# RemoteControl.net
KiCad netlist of a schematic drawn in EAGLE
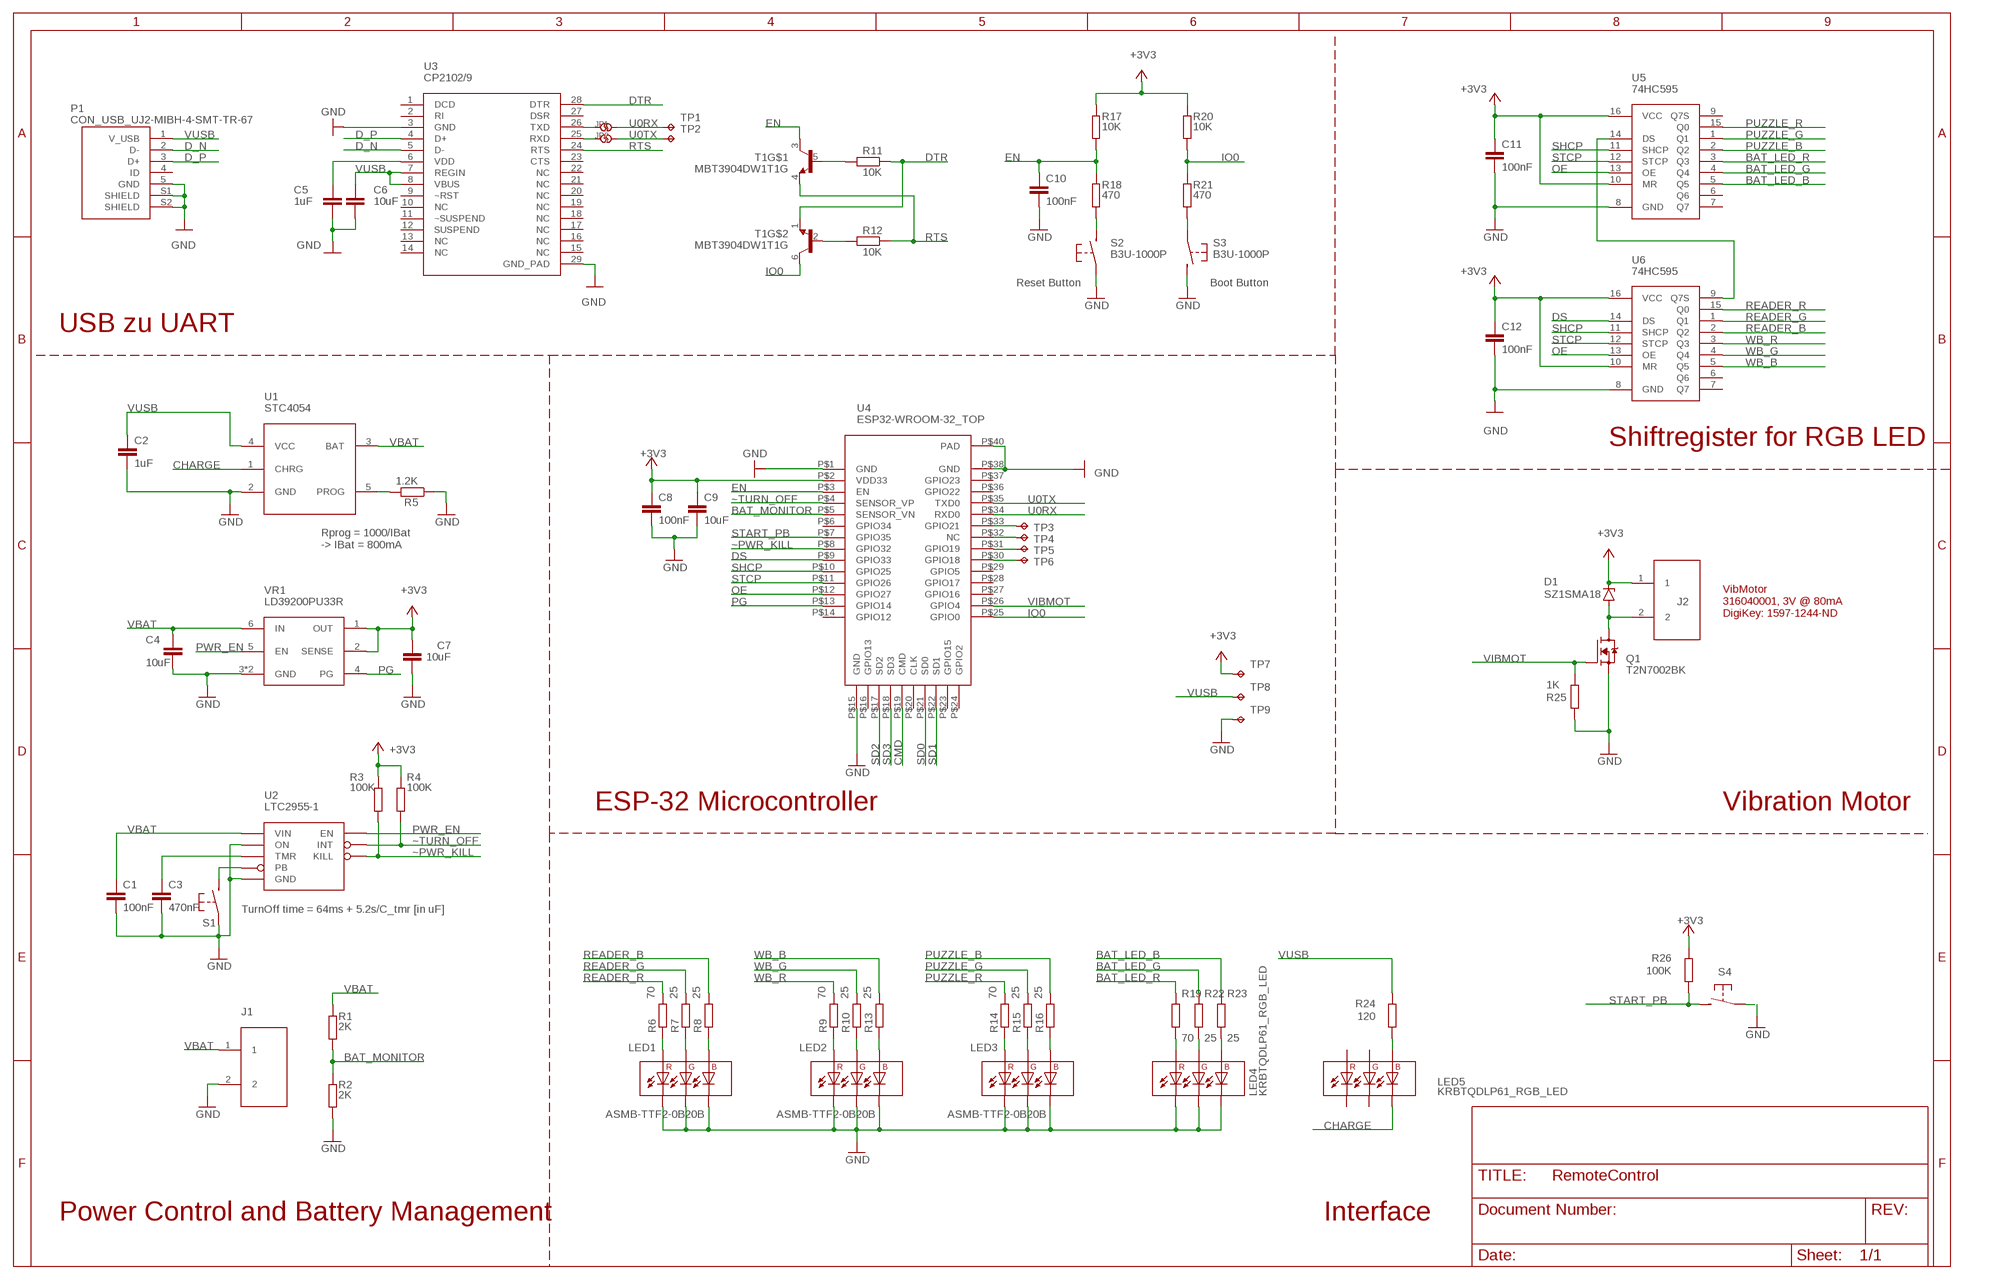
[diagram p0: schematic, sheet 1]

(export (version "E")
  (design (tool "Eeschema 10.0.6"))
  (components
    (comp (ref "C1")
      (value "100nF")
      (footprint "eagle-import:0603")
      (libsource (lib "eagle-import") (part "CAP_0603"))
    )
    (comp (ref "C2")
      (value "1uF")
      (footprint "eagle-import:0603")
      (libsource (lib "eagle-import") (part "CAP_0603"))
    )
    (comp (ref "C3")
      (value "470nF")
      (footprint "eagle-import:0603")
      (libsource (lib "eagle-import") (part "CAP_0603"))
    )
    (comp (ref "C4")
      (value "10uF")
      (footprint "eagle-import:0603")
      (libsource (lib "eagle-import") (part "CAP_0603"))
    )
    (comp (ref "C5")
      (value "1uF")
      (footprint "eagle-import:0603")
      (libsource (lib "eagle-import") (part "CAP_0603"))
    )
    (comp (ref "C6")
      (value "10uF")
      (footprint "eagle-import:0603")
      (libsource (lib "eagle-import") (part "CAP_0603"))
    )
    (comp (ref "C7")
      (value "10uF")
      (footprint "eagle-import:0603")
      (libsource (lib "eagle-import") (part "CAP_0603"))
    )
    (comp (ref "C8")
      (value "100nF")
      (footprint "eagle-import:0603")
      (libsource (lib "eagle-import") (part "CAP_0603"))
    )
    (comp (ref "C9")
      (value "10uF")
      (footprint "eagle-import:0603")
      (libsource (lib "eagle-import") (part "CAP_0603"))
    )
    (comp (ref "C10")
      (value "100nF")
      (footprint "eagle-import:0603")
      (libsource (lib "eagle-import") (part "CAP_0603"))
    )
    (comp (ref "C11")
      (value "100nF")
      (footprint "eagle-import:0603")
      (libsource (lib "eagle-import") (part "CAP_0603"))
    )
    (comp (ref "C12")
      (value "100nF")
      (footprint "eagle-import:0603")
      (libsource (lib "eagle-import") (part "CAP_0603"))
    )
    (comp (ref "D1")
      (value "SZ1SMA18")
      (footprint "eagle-import:SMA-2")
      (libsource (lib "eagle-import") (part "SZ1SMA18AT3G_Z_DIODE"))
    )
    (comp (ref "J1")
      (value "CON_2")
      (footprint "eagle-import:CON_2")
      (libsource (lib "eagle-import") (part "CON_2"))
    )
    (comp (ref "J2")
      (value "CON_2")
      (footprint "eagle-import:CON_2")
      (libsource (lib "eagle-import") (part "CON_2"))
    )
    (comp (ref "JP1")
      (value "SOLDER_JUMPER")
      (footprint "eagle-import:SOLDER_JUMPER")
      (libsource (lib "eagle-import") (part "SOLDER_JUMPER"))
    )
    (comp (ref "JP2")
      (value "SOLDER_JUMPER")
      (footprint "eagle-import:SOLDER_JUMPER")
      (libsource (lib "eagle-import") (part "SOLDER_JUMPER"))
    )
    (comp (ref "LED1")
      (value "ASMB-TTF2-0B20B")
      (footprint "eagle-import:ASMB-TTF2-0B20B_RGB_LED")
      (libsource (lib "eagle-import") (part "ASMB-TTF2-0B20B_RGB_LED"))
    )
    (comp (ref "LED2")
      (value "ASMB-TTF2-0B20B")
      (footprint "eagle-import:ASMB-TTF2-0B20B_RGB_LED")
      (libsource (lib "eagle-import") (part "ASMB-TTF2-0B20B_RGB_LED"))
    )
    (comp (ref "LED3")
      (value "ASMB-TTF2-0B20B")
      (footprint "eagle-import:ASMB-TTF2-0B20B_RGB_LED")
      (libsource (lib "eagle-import") (part "ASMB-TTF2-0B20B_RGB_LED"))
    )
    (comp (ref "LED4")
      (value "KRBTQDLP61_RGB_LED")
      (footprint "eagle-import:KRBTQDLP61_RGB_LED")
      (libsource (lib "eagle-import") (part "KRBTQDLP61_RGB_LED"))
    )
    (comp (ref "LED5")
      (value "KRBTQDLP61_RGB_LED")
      (footprint "eagle-import:KRBTQDLP61_RGB_LED")
      (libsource (lib "eagle-import") (part "KRBTQDLP61_RGB_LED"))
    )
    (comp (ref "P1")
      (value "CON_USB_UJ2-MIBH-4-SMT-TR-67")
      (footprint "eagle-import:CON_USB_UJ2-MIBH-4-SMT-TR-67")
      (libsource (lib "eagle-import") (part "CON_USB_UJ2-MIBH-4-SMT-TR-67"))
    )
    (comp (ref "Q1")
      (value "T2N7002BK")
      (footprint "eagle-import:SOT23-3")
      (libsource (lib "eagle-import") (part "T2N7002BK"))
    )
    (comp (ref "R1")
      (value "2K")
      (footprint "eagle-import:0603")
      (libsource (lib "eagle-import") (part "RES_0603"))
    )
    (comp (ref "R2")
      (value "2K")
      (footprint "eagle-import:0603")
      (libsource (lib "eagle-import") (part "RES_0603"))
    )
    (comp (ref "R3")
      (value "100K")
      (footprint "eagle-import:0603")
      (libsource (lib "eagle-import") (part "RES_0603"))
    )
    (comp (ref "R4")
      (value "100K")
      (footprint "eagle-import:0603")
      (libsource (lib "eagle-import") (part "RES_0603"))
    )
    (comp (ref "R5")
      (value "1.2K")
      (footprint "eagle-import:0603")
      (libsource (lib "eagle-import") (part "RES_0603"))
    )
    (comp (ref "R6")
      (value "70")
      (footprint "eagle-import:0603")
      (libsource (lib "eagle-import") (part "RES_0603"))
    )
    (comp (ref "R7")
      (value "25")
      (footprint "eagle-import:0603")
      (libsource (lib "eagle-import") (part "RES_0603"))
    )
    (comp (ref "R8")
      (value "25")
      (footprint "eagle-import:0603")
      (libsource (lib "eagle-import") (part "RES_0603"))
    )
    (comp (ref "R9")
      (value "70")
      (footprint "eagle-import:0603")
      (libsource (lib "eagle-import") (part "RES_0603"))
    )
    (comp (ref "R10")
      (value "25")
      (footprint "eagle-import:0603")
      (libsource (lib "eagle-import") (part "RES_0603"))
    )
    (comp (ref "R11")
      (value "10K")
      (footprint "eagle-import:0603")
      (libsource (lib "eagle-import") (part "RES_0603"))
    )
    (comp (ref "R12")
      (value "10K")
      (footprint "eagle-import:0603")
      (libsource (lib "eagle-import") (part "RES_0603"))
    )
    (comp (ref "R13")
      (value "25")
      (footprint "eagle-import:0603")
      (libsource (lib "eagle-import") (part "RES_0603"))
    )
    (comp (ref "R14")
      (value "70")
      (footprint "eagle-import:0603")
      (libsource (lib "eagle-import") (part "RES_0603"))
    )
    (comp (ref "R15")
      (value "25")
      (footprint "eagle-import:0603")
      (libsource (lib "eagle-import") (part "RES_0603"))
    )
    (comp (ref "R16")
      (value "25")
      (footprint "eagle-import:0603")
      (libsource (lib "eagle-import") (part "RES_0603"))
    )
    (comp (ref "R17")
      (value "10K")
      (footprint "eagle-import:0603")
      (libsource (lib "eagle-import") (part "RES_0603"))
    )
    (comp (ref "R18")
      (value "470")
      (footprint "eagle-import:0603")
      (libsource (lib "eagle-import") (part "RES_0603"))
    )
    (comp (ref "R19")
      (value "70")
      (footprint "eagle-import:0603")
      (libsource (lib "eagle-import") (part "RES_0603"))
    )
    (comp (ref "R20")
      (value "10K")
      (footprint "eagle-import:0603")
      (libsource (lib "eagle-import") (part "RES_0603"))
    )
    (comp (ref "R21")
      (value "470")
      (footprint "eagle-import:0603")
      (libsource (lib "eagle-import") (part "RES_0603"))
    )
    (comp (ref "R22")
      (value "25")
      (footprint "eagle-import:0603")
      (libsource (lib "eagle-import") (part "RES_0603"))
    )
    (comp (ref "R23")
      (value "25")
      (footprint "eagle-import:0603")
      (libsource (lib "eagle-import") (part "RES_0603"))
    )
    (comp (ref "R24")
      (value "120")
      (footprint "eagle-import:0603")
      (libsource (lib "eagle-import") (part "RES_0603"))
    )
    (comp (ref "R25")
      (value "1K")
      (footprint "eagle-import:0603")
      (libsource (lib "eagle-import") (part "RES_0603"))
    )
    (comp (ref "R26")
      (value "100K")
      (footprint "eagle-import:0603")
      (libsource (lib "eagle-import") (part "RES_0603"))
    )
    (comp (ref "S1")
      (value "EG5358CT-ND_PB")
      (footprint "eagle-import:EG5358CT-ND_PB")
      (libsource (lib "eagle-import") (part "EG5358CT-ND_PB"))
    )
    (comp (ref "S2")
      (value "B3U-1000P")
      (footprint "eagle-import:B3U-1000P")
      (libsource (lib "eagle-import") (part "BUTTON_B3U-1000P"))
    )
    (comp (ref "S3")
      (value "B3U-1000P")
      (footprint "eagle-import:B3U-1000P")
      (libsource (lib "eagle-import") (part "BUTTON_B3U-1000P"))
    )
    (comp (ref "S4")
      (value "TL3313AF160QG_2")
      (footprint "eagle-import:TL3313AF160QG_2")
      (libsource (lib "eagle-import") (part "BUTTON_TL3313AF160QG_2"))
    )
    (comp (ref "T1")
      (value "MBT3904DW1T1G")
      (footprint "eagle-import:SOT23-6")
      (libsource (lib "eagle-import") (part "MBT3904DW1T1G"))
    )
    (comp (ref "TP1")
      (value "TP")
      (footprint "eagle-import:TEST_PAD")
      (libsource (lib "eagle-import") (part "TP"))
    )
    (comp (ref "TP2")
      (value "TP")
      (footprint "eagle-import:TEST_PAD")
      (libsource (lib "eagle-import") (part "TP"))
    )
    (comp (ref "TP3")
      (value "TP")
      (footprint "eagle-import:TEST_PAD")
      (libsource (lib "eagle-import") (part "TP"))
    )
    (comp (ref "TP4")
      (value "TP")
      (footprint "eagle-import:TEST_PAD")
      (libsource (lib "eagle-import") (part "TP"))
    )
    (comp (ref "TP5")
      (value "TP")
      (footprint "eagle-import:TEST_PAD")
      (libsource (lib "eagle-import") (part "TP"))
    )
    (comp (ref "TP6")
      (value "TP")
      (footprint "eagle-import:TEST_PAD")
      (libsource (lib "eagle-import") (part "TP"))
    )
    (comp (ref "TP7")
      (value "TP")
      (footprint "eagle-import:TEST_PAD")
      (libsource (lib "eagle-import") (part "TP"))
    )
    (comp (ref "TP8")
      (value "TP")
      (footprint "eagle-import:TEST_PAD")
      (libsource (lib "eagle-import") (part "TP"))
    )
    (comp (ref "TP9")
      (value "TP")
      (footprint "eagle-import:TEST_PAD")
      (libsource (lib "eagle-import") (part "TP"))
    )
    (comp (ref "U1")
      (value "STC4054")
      (footprint "eagle-import:TSOT23-5L")
      (libsource (lib "eagle-import") (part "STC4054_BAT_CHARGER"))
    )
    (comp (ref "U2")
      (value "LTC2955-1")
      (footprint "eagle-import:SOT23-8")
      (libsource (lib "eagle-import") (part "LTC2955-1_ON/OFF_CTLR"))
    )
    (comp (ref "U3")
      (value "CP2102/9")
      (footprint "eagle-import:QFN-28")
      (libsource (lib "eagle-import") (part "CP2102/9"))
    )
    (comp (ref "U4")
      (value "ESP32-WROOM-32_TOP")
      (footprint "eagle-import:ESP32-WROOM-32_TOP")
      (libsource (lib "eagle-import") (part "ESP32-WROOM-32_TOP"))
    )
    (comp (ref "U5")
      (value "74HC595")
      (footprint "eagle-import:SOIC-16")
      (libsource (lib "eagle-import") (part "74HC595_SHIFTREGISTER"))
    )
    (comp (ref "U6")
      (value "74HC595")
      (footprint "eagle-import:SOIC-16")
      (libsource (lib "eagle-import") (part "74HC595_SHIFTREGISTER"))
    )
    (comp (ref "VR1")
      (value "LD39200PU33R")
      (footprint "eagle-import:DFN-6")
      (libsource (lib "eagle-import") (part "LD39200PU33R_V-REG"))
    )
  )
  (nets
    (net (code "1") (name "+3V3") (class "Default")
      (node (ref "C11") (pin "1") (pinfunction "1_1") (pintype "passive"))
      (node (ref "C12") (pin "1") (pinfunction "1_1") (pintype "passive"))
      (node (ref "C7") (pin "2") (pinfunction "2_2") (pintype "passive"))
      (node (ref "C8") (pin "1") (pinfunction "1_1") (pintype "passive"))
      (node (ref "C9") (pin "1") (pinfunction "1_1") (pintype "passive"))
      (node (ref "D1") (pin "1") (pinfunction "C_1") (pintype "passive"))
      (node (ref "J2") (pin "1") (pinfunction "1_1") (pintype "bidirectional"))
      (node (ref "R17") (pin "2") (pinfunction "2_2") (pintype "passive"))
      (node (ref "R20") (pin "2") (pinfunction "2_2") (pintype "passive"))
      (node (ref "R26") (pin "2") (pinfunction "2_2") (pintype "passive"))
      (node (ref "R3") (pin "1") (pinfunction "1_1") (pintype "passive"))
      (node (ref "R4") (pin "1") (pinfunction "1_1") (pintype "passive"))
      (node (ref "TP7") (pin "TP") (pinfunction "TP_TP") (pintype "input"))
      (node (ref "U4") (pin "P$2") (pinfunction "VDD33_P$2") (pintype "bidirectional"))
      (node (ref "U5") (pin "10") (pinfunction "MR_10") (pintype "bidirectional"))
      (node (ref "U5") (pin "16") (pinfunction "VCC_16") (pintype "bidirectional"))
      (node (ref "U6") (pin "10") (pinfunction "MR_10") (pintype "bidirectional"))
      (node (ref "U6") (pin "16") (pinfunction "VCC_16") (pintype "bidirectional"))
      (node (ref "VR1") (pin "1") (pinfunction "OUT_1") (pintype "bidirectional"))
      (node (ref "VR1") (pin "2") (pinfunction "SENSE_2") (pintype "bidirectional"))
    )
    (net (code "2") (name "/BAT_LED_B") (class "Default")
      (node (ref "R23") (pin "2") (pinfunction "2_2") (pintype "passive"))
      (node (ref "U5") (pin "5") (pinfunction "Q5_5") (pintype "bidirectional"))
    )
    (net (code "3") (name "/BAT_LED_G") (class "Default")
      (node (ref "R22") (pin "2") (pinfunction "2_2") (pintype "passive"))
      (node (ref "U5") (pin "4") (pinfunction "Q4_4") (pintype "bidirectional"))
    )
    (net (code "4") (name "/BAT_LED_R") (class "Default")
      (node (ref "R19") (pin "2") (pinfunction "2_2") (pintype "passive"))
      (node (ref "U5") (pin "3") (pinfunction "Q3_3") (pintype "bidirectional"))
    )
    (net (code "5") (name "/BAT_MONITOR") (class "Default")
      (node (ref "R1") (pin "2") (pinfunction "2_2") (pintype "passive"))
      (node (ref "R2") (pin "1") (pinfunction "1_1") (pintype "passive"))
      (node (ref "U4") (pin "P$5") (pinfunction "SENSOR_VN_P$5") (pintype "bidirectional"))
    )
    (net (code "6") (name "/CHARGE") (class "Default")
      (node (ref "LED5") (pin "P$4") (pinfunction "BC_P$4") (pintype "passive"))
      (node (ref "U1") (pin "1") (pinfunction "CHRG_1") (pintype "bidirectional"))
    )
    (net (code "7") (name "/CMD") (class "Default")
      (node (ref "U4") (pin "P$19") (pinfunction "CMD_P$19") (pintype "bidirectional"))
    )
    (net (code "8") (name "/DS") (class "Default")
      (node (ref "U4") (pin "P$9") (pinfunction "GPIO33_P$9") (pintype "bidirectional"))
      (node (ref "U6") (pin "14") (pinfunction "DS_14") (pintype "bidirectional"))
    )
    (net (code "9") (name "/DTR") (class "Default")
      (node (ref "R11") (pin "1") (pinfunction "1_1") (pintype "passive"))
      (node (ref "T1") (pin "1") (pinfunction "E_1") (pintype "passive"))
      (node (ref "U3") (pin "28") (pinfunction "DTR_28") (pintype "bidirectional"))
    )
    (net (code "10") (name "/D_N") (class "Default")
      (node (ref "P1") (pin "2") (pinfunction "D-_2") (pintype "bidirectional"))
      (node (ref "U3") (pin "5") (pinfunction "D-_5") (pintype "bidirectional"))
    )
    (net (code "11") (name "/D_P") (class "Default")
      (node (ref "P1") (pin "3") (pinfunction "D+_3") (pintype "bidirectional"))
      (node (ref "U3") (pin "4") (pinfunction "D+_4") (pintype "bidirectional"))
    )
    (net (code "12") (name "/EN") (class "Default")
      (node (ref "C10") (pin "1") (pinfunction "1_1") (pintype "passive"))
      (node (ref "R17") (pin "1") (pinfunction "1_1") (pintype "passive"))
      (node (ref "R18") (pin "2") (pinfunction "2_2") (pintype "passive"))
      (node (ref "T1") (pin "3") (pinfunction "C_3") (pintype "passive"))
      (node (ref "U4") (pin "P$3") (pinfunction "EN_P$3") (pintype "bidirectional"))
    )
    (net (code "13") (name "/IO0") (class "Default")
      (node (ref "R20") (pin "1") (pinfunction "1_1") (pintype "passive"))
      (node (ref "R21") (pin "2") (pinfunction "2_2") (pintype "passive"))
      (node (ref "T1") (pin "6") (pinfunction "C_6") (pintype "passive"))
      (node (ref "U4") (pin "P$25") (pinfunction "GPIO0_P$25") (pintype "bidirectional"))
    )
    (net (code "14") (name "/OE") (class "Default")
      (node (ref "U4") (pin "P$12") (pinfunction "GPIO27_P$12") (pintype "bidirectional"))
      (node (ref "U5") (pin "13") (pinfunction "OE_13") (pintype "bidirectional"))
      (node (ref "U6") (pin "13") (pinfunction "OE_13") (pintype "bidirectional"))
    )
    (net (code "15") (name "/PG") (class "Default")
      (node (ref "U4") (pin "P$13") (pinfunction "GPIO14_P$13") (pintype "bidirectional"))
      (node (ref "VR1") (pin "4") (pinfunction "PG_4") (pintype "bidirectional"))
    )
    (net (code "16") (name "/PUZZLE_B") (class "Default")
      (node (ref "R16") (pin "2") (pinfunction "2_2") (pintype "passive"))
      (node (ref "U5") (pin "2") (pinfunction "Q2_2") (pintype "bidirectional"))
    )
    (net (code "17") (name "/PUZZLE_G") (class "Default")
      (node (ref "R15") (pin "2") (pinfunction "2_2") (pintype "passive"))
      (node (ref "U5") (pin "1") (pinfunction "Q1_1") (pintype "bidirectional"))
    )
    (net (code "18") (name "/PUZZLE_R") (class "Default")
      (node (ref "R14") (pin "2") (pinfunction "2_2") (pintype "passive"))
      (node (ref "U5") (pin "15") (pinfunction "Q0_15") (pintype "bidirectional"))
    )
    (net (code "19") (name "/PWR_EN") (class "Default")
      (node (ref "U2") (pin "7") (pinfunction "EN_7") (pintype "bidirectional"))
      (node (ref "VR1") (pin "5") (pinfunction "EN_5") (pintype "bidirectional"))
    )
    (net (code "20") (name "/READER_B") (class "Default")
      (node (ref "R8") (pin "2") (pinfunction "2_2") (pintype "passive"))
      (node (ref "U6") (pin "2") (pinfunction "Q2_2") (pintype "bidirectional"))
    )
    (net (code "21") (name "/READER_G") (class "Default")
      (node (ref "R7") (pin "2") (pinfunction "2_2") (pintype "passive"))
      (node (ref "U6") (pin "1") (pinfunction "Q1_1") (pintype "bidirectional"))
    )
    (net (code "22") (name "/READER_R") (class "Default")
      (node (ref "R6") (pin "2") (pinfunction "2_2") (pintype "passive"))
      (node (ref "U6") (pin "15") (pinfunction "Q0_15") (pintype "bidirectional"))
    )
    (net (code "23") (name "/RTS") (class "Default")
      (node (ref "R12") (pin "1") (pinfunction "1_1") (pintype "passive"))
      (node (ref "T1") (pin "4") (pinfunction "E_4") (pintype "passive"))
      (node (ref "U3") (pin "24") (pinfunction "RTS_24") (pintype "bidirectional"))
    )
    (net (code "24") (name "/SD0") (class "Default")
      (node (ref "U4") (pin "P$21") (pinfunction "SD0_P$21") (pintype "bidirectional"))
    )
    (net (code "25") (name "/SD1") (class "Default")
      (node (ref "U4") (pin "P$22") (pinfunction "SD1_P$22") (pintype "bidirectional"))
    )
    (net (code "26") (name "/SD2") (class "Default")
      (node (ref "U4") (pin "P$17") (pinfunction "SD2_P$17") (pintype "bidirectional"))
    )
    (net (code "27") (name "/SD3") (class "Default")
      (node (ref "U4") (pin "P$18") (pinfunction "SD3_P$18") (pintype "bidirectional"))
    )
    (net (code "28") (name "/SHCP") (class "Default")
      (node (ref "U4") (pin "P$10") (pinfunction "GPIO25_P$10") (pintype "bidirectional"))
      (node (ref "U5") (pin "11") (pinfunction "SHCP_11") (pintype "bidirectional"))
      (node (ref "U6") (pin "11") (pinfunction "SHCP_11") (pintype "bidirectional"))
    )
    (net (code "29") (name "/START_PB") (class "Default")
      (node (ref "R26") (pin "1") (pinfunction "1_1") (pintype "passive"))
      (node (ref "S4") (pin "3") (pinfunction "S_3") (pintype "passive"))
      (node (ref "S4") (pin "4") (pinfunction "S_4") (pintype "passive"))
      (node (ref "U4") (pin "P$7") (pinfunction "GPIO35_P$7") (pintype "bidirectional"))
    )
    (net (code "30") (name "/STCP") (class "Default")
      (node (ref "U4") (pin "P$11") (pinfunction "GPIO26_P$11") (pintype "bidirectional"))
      (node (ref "U5") (pin "12") (pinfunction "STCP_12") (pintype "bidirectional"))
      (node (ref "U6") (pin "12") (pinfunction "STCP_12") (pintype "bidirectional"))
    )
    (net (code "31") (name "/U0RX") (class "Default")
      (node (ref "JP1") (pin "P$2") (pinfunction "P$2_P$2") (pintype "bidirectional"))
      (node (ref "TP1") (pin "TP") (pinfunction "TP_TP") (pintype "input"))
      (node (ref "U4") (pin "P$34") (pinfunction "RXD0_P$34") (pintype "bidirectional"))
    )
    (net (code "32") (name "/U0TX") (class "Default")
      (node (ref "JP2") (pin "P$2") (pinfunction "P$2_P$2") (pintype "bidirectional"))
      (node (ref "TP2") (pin "TP") (pinfunction "TP_TP") (pintype "input"))
      (node (ref "U4") (pin "P$35") (pinfunction "TXD0_P$35") (pintype "bidirectional"))
    )
    (net (code "33") (name "/VBAT") (class "Default")
      (node (ref "C1") (pin "1") (pinfunction "1_1") (pintype "passive"))
      (node (ref "C4") (pin "1") (pinfunction "1_1") (pintype "passive"))
      (node (ref "J1") (pin "1") (pinfunction "1_1") (pintype "bidirectional"))
      (node (ref "R1") (pin "1") (pinfunction "1_1") (pintype "passive"))
      (node (ref "U1") (pin "3") (pinfunction "BAT_3") (pintype "bidirectional"))
      (node (ref "U2") (pin "6") (pinfunction "VIN_6") (pintype "bidirectional"))
      (node (ref "VR1") (pin "6") (pinfunction "IN_6") (pintype "bidirectional"))
    )
    (net (code "34") (name "/VIBMOT") (class "Default")
      (node (ref "Q1") (pin "1") (pinfunction "G_1") (pintype "passive"))
      (node (ref "R25") (pin "2") (pinfunction "2_2") (pintype "passive"))
      (node (ref "U4") (pin "P$26") (pinfunction "GPIO4_P$26") (pintype "bidirectional"))
    )
    (net (code "35") (name "/VUSB") (class "Default")
      (node (ref "C2") (pin "1") (pinfunction "1_1") (pintype "passive"))
      (node (ref "C6") (pin "1") (pinfunction "1_1") (pintype "passive"))
      (node (ref "P1") (pin "1") (pinfunction "V_USB_1") (pintype "bidirectional"))
      (node (ref "R24") (pin "2") (pinfunction "2_2") (pintype "passive"))
      (node (ref "TP8") (pin "TP") (pinfunction "TP_TP") (pintype "input"))
      (node (ref "U1") (pin "4") (pinfunction "VCC_4") (pintype "bidirectional"))
      (node (ref "U3") (pin "7") (pinfunction "REGIN_7") (pintype "bidirectional"))
      (node (ref "U3") (pin "8") (pinfunction "VBUS_8") (pintype "bidirectional"))
    )
    (net (code "36") (name "/WB_B") (class "Default")
      (node (ref "R13") (pin "2") (pinfunction "2_2") (pintype "passive"))
      (node (ref "U6") (pin "5") (pinfunction "Q5_5") (pintype "bidirectional"))
    )
    (net (code "37") (name "/WB_G") (class "Default")
      (node (ref "R10") (pin "2") (pinfunction "2_2") (pintype "passive"))
      (node (ref "U6") (pin "4") (pinfunction "Q4_4") (pintype "bidirectional"))
    )
    (net (code "38") (name "/WB_R") (class "Default")
      (node (ref "R9") (pin "2") (pinfunction "2_2") (pintype "passive"))
      (node (ref "U6") (pin "3") (pinfunction "Q3_3") (pintype "bidirectional"))
    )
    (net (code "39") (name "/~{PWR_KILL}") (class "Default")
      (node (ref "R3") (pin "2") (pinfunction "2_2") (pintype "passive"))
      (node (ref "U2") (pin "2") (pinfunction "KILL_2") (pintype "bidirectional"))
      (node (ref "U4") (pin "P$8") (pinfunction "GPIO32_P$8") (pintype "bidirectional"))
    )
    (net (code "40") (name "/~{TURN_OFF}") (class "Default")
      (node (ref "R4") (pin "2") (pinfunction "2_2") (pintype "passive"))
      (node (ref "U2") (pin "8") (pinfunction "INT_8") (pintype "bidirectional"))
      (node (ref "U4") (pin "P$4") (pinfunction "SENSOR_VP_P$4") (pintype "bidirectional"))
    )
    (net (code "41") (name "GND") (class "Default")
      (node (ref "C1") (pin "2") (pinfunction "2_2") (pintype "passive"))
      (node (ref "C10") (pin "2") (pinfunction "2_2") (pintype "passive"))
      (node (ref "C11") (pin "2") (pinfunction "2_2") (pintype "passive"))
      (node (ref "C12") (pin "2") (pinfunction "2_2") (pintype "passive"))
      (node (ref "C2") (pin "2") (pinfunction "2_2") (pintype "passive"))
      (node (ref "C3") (pin "2") (pinfunction "2_2") (pintype "passive"))
      (node (ref "C4") (pin "2") (pinfunction "2_2") (pintype "passive"))
      (node (ref "C5") (pin "2") (pinfunction "2_2") (pintype "passive"))
      (node (ref "C6") (pin "2") (pinfunction "2_2") (pintype "passive"))
      (node (ref "C7") (pin "1") (pinfunction "1_1") (pintype "passive"))
      (node (ref "C8") (pin "2") (pinfunction "2_2") (pintype "passive"))
      (node (ref "C9") (pin "2") (pinfunction "2_2") (pintype "passive"))
      (node (ref "J1") (pin "2") (pinfunction "2_2") (pintype "bidirectional"))
      (node (ref "LED1") (pin "BC") (pinfunction "BC_BC") (pintype "passive"))
      (node (ref "LED1") (pin "GC") (pinfunction "GC_GC") (pintype "passive"))
      (node (ref "LED1") (pin "RC") (pinfunction "RC_RC") (pintype "passive"))
      (node (ref "LED2") (pin "BC") (pinfunction "BC_BC") (pintype "passive"))
      (node (ref "LED2") (pin "GC") (pinfunction "GC_GC") (pintype "passive"))
      (node (ref "LED2") (pin "RC") (pinfunction "RC_RC") (pintype "passive"))
      (node (ref "LED3") (pin "BC") (pinfunction "BC_BC") (pintype "passive"))
      (node (ref "LED3") (pin "GC") (pinfunction "GC_GC") (pintype "passive"))
      (node (ref "LED3") (pin "RC") (pinfunction "RC_RC") (pintype "passive"))
      (node (ref "LED4") (pin "P$3") (pinfunction "GC_P$3") (pintype "passive"))
      (node (ref "LED4") (pin "P$4") (pinfunction "BC_P$4") (pintype "passive"))
      (node (ref "LED4") (pin "P$6") (pinfunction "RC_P$6") (pintype "passive"))
      (node (ref "P1") (pin "5") (pinfunction "GND_5") (pintype "bidirectional"))
      (node (ref "P1") (pin "S1") (pinfunction "SHIELD_S1") (pintype "bidirectional"))
      (node (ref "P1") (pin "S2") (pinfunction "SHIELD_S2") (pintype "bidirectional"))
      (node (ref "Q1") (pin "2") (pinfunction "S_2") (pintype "passive"))
      (node (ref "R2") (pin "2") (pinfunction "2_2") (pintype "passive"))
      (node (ref "R25") (pin "1") (pinfunction "1_1") (pintype "passive"))
      (node (ref "R5") (pin "1") (pinfunction "1_1") (pintype "passive"))
      (node (ref "S1") (pin "1") (pinfunction "P_1") (pintype "passive"))
      (node (ref "S1") (pin "S1") (pinfunction "P_S1") (pintype "passive"))
      (node (ref "S1") (pin "S2") (pinfunction "P_S2") (pintype "passive"))
      (node (ref "S2") (pin "P$1") (pinfunction "P_P$1") (pintype "passive"))
      (node (ref "S3") (pin "P$2") (pinfunction "S_P$2") (pintype "passive"))
      (node (ref "S4") (pin "1") (pinfunction "P_1") (pintype "passive"))
      (node (ref "S4") (pin "2") (pinfunction "P_2") (pintype "passive"))
      (node (ref "TP9") (pin "TP") (pinfunction "TP_TP") (pintype "input"))
      (node (ref "U1") (pin "2") (pinfunction "GND_2") (pintype "bidirectional"))
      (node (ref "U2") (pin "1") (pinfunction "ON_1") (pintype "bidirectional"))
      (node (ref "U2") (pin "4") (pinfunction "GND_4") (pintype "bidirectional"))
      (node (ref "U3") (pin "29") (pinfunction "GND_PAD_29") (pintype "bidirectional"))
      (node (ref "U3") (pin "3") (pinfunction "GND_3") (pintype "bidirectional"))
      (node (ref "U4") (pin "P$1") (pinfunction "GND_P$1") (pintype "bidirectional"))
      (node (ref "U4") (pin "P$15") (pinfunction "GND_P$15") (pintype "bidirectional"))
      (node (ref "U4") (pin "P$38") (pinfunction "GND_P$38") (pintype "bidirectional"))
      (node (ref "U4") (pin "P$40") (pinfunction "PAD_P$40") (pintype "bidirectional"))
      (node (ref "U5") (pin "8") (pinfunction "GND_8") (pintype "bidirectional"))
      (node (ref "U6") (pin "8") (pinfunction "GND_8") (pintype "bidirectional"))
      (node (ref "VR1") (pin "3") (pinfunction "GND_3") (pintype "bidirectional"))
      (node (ref "VR1") (pin "7") (pinfunction "GND_7") (pintype "bidirectional"))
    )
    (net (code "42") (name "Net-(D1-A)") (class "Default")
      (node (ref "D1") (pin "2") (pinfunction "A_2") (pintype "passive"))
      (node (ref "J2") (pin "2") (pinfunction "2_2") (pintype "bidirectional"))
      (node (ref "Q1") (pin "3") (pinfunction "D_3") (pintype "passive"))
    )
    (net (code "43") (name "Net-(LED1-PadBA)") (class "Default")
      (node (ref "LED1") (pin "BA") (pinfunction "BA_BA") (pintype "passive"))
      (node (ref "R8") (pin "1") (pinfunction "1_1") (pintype "passive"))
    )
    (net (code "44") (name "Net-(LED1-PadGA)") (class "Default")
      (node (ref "LED1") (pin "GA") (pinfunction "GA_GA") (pintype "passive"))
      (node (ref "R7") (pin "1") (pinfunction "1_1") (pintype "passive"))
    )
    (net (code "45") (name "Net-(LED1-PadRA)") (class "Default")
      (node (ref "LED1") (pin "RA") (pinfunction "RA_RA") (pintype "passive"))
      (node (ref "R6") (pin "1") (pinfunction "1_1") (pintype "passive"))
    )
    (net (code "46") (name "Net-(LED2-PadBA)") (class "Default")
      (node (ref "LED2") (pin "BA") (pinfunction "BA_BA") (pintype "passive"))
      (node (ref "R13") (pin "1") (pinfunction "1_1") (pintype "passive"))
    )
    (net (code "47") (name "Net-(LED2-PadGA)") (class "Default")
      (node (ref "LED2") (pin "GA") (pinfunction "GA_GA") (pintype "passive"))
      (node (ref "R10") (pin "1") (pinfunction "1_1") (pintype "passive"))
    )
    (net (code "48") (name "Net-(LED2-PadRA)") (class "Default")
      (node (ref "LED2") (pin "RA") (pinfunction "RA_RA") (pintype "passive"))
      (node (ref "R9") (pin "1") (pinfunction "1_1") (pintype "passive"))
    )
    (net (code "49") (name "Net-(LED3-PadBA)") (class "Default")
      (node (ref "LED3") (pin "BA") (pinfunction "BA_BA") (pintype "passive"))
      (node (ref "R16") (pin "1") (pinfunction "1_1") (pintype "passive"))
    )
    (net (code "50") (name "Net-(LED3-PadGA)") (class "Default")
      (node (ref "LED3") (pin "GA") (pinfunction "GA_GA") (pintype "passive"))
      (node (ref "R15") (pin "1") (pinfunction "1_1") (pintype "passive"))
    )
    (net (code "51") (name "Net-(LED3-PadRA)") (class "Default")
      (node (ref "LED3") (pin "RA") (pinfunction "RA_RA") (pintype "passive"))
      (node (ref "R14") (pin "1") (pinfunction "1_1") (pintype "passive"))
    )
    (net (code "52") (name "Net-(LED4-BA)") (class "Default")
      (node (ref "LED4") (pin "P$2") (pinfunction "BA_P$2") (pintype "passive"))
      (node (ref "R23") (pin "1") (pinfunction "1_1") (pintype "passive"))
    )
    (net (code "53") (name "Net-(LED4-GA)") (class "Default")
      (node (ref "LED4") (pin "P$1") (pinfunction "GA_P$1") (pintype "passive"))
      (node (ref "R22") (pin "1") (pinfunction "1_1") (pintype "passive"))
    )
    (net (code "54") (name "Net-(LED4-RA)") (class "Default")
      (node (ref "LED4") (pin "P$5") (pinfunction "RA_P$5") (pintype "passive"))
      (node (ref "R19") (pin "1") (pinfunction "1_1") (pintype "passive"))
    )
    (net (code "55") (name "Net-(LED5-BA)") (class "Default")
      (node (ref "LED5") (pin "P$2") (pinfunction "BA_P$2") (pintype "passive"))
      (node (ref "R24") (pin "1") (pinfunction "1_1") (pintype "passive"))
    )
    (net (code "56") (name "Net-(S1-S)") (class "Default")
      (node (ref "S1") (pin "2") (pinfunction "S_2") (pintype "passive"))
      (node (ref "U2") (pin "5") (pinfunction "PB_5") (pintype "bidirectional"))
    )
    (net (code "57") (name "Net-(S2-S)") (class "Default")
      (node (ref "R18") (pin "1") (pinfunction "1_1") (pintype "passive"))
      (node (ref "S2") (pin "P$2") (pinfunction "S_P$2") (pintype "passive"))
    )
    (net (code "58") (name "Net-(S3-P)") (class "Default")
      (node (ref "R21") (pin "1") (pinfunction "1_1") (pintype "passive"))
      (node (ref "S3") (pin "P$1") (pinfunction "P_P$1") (pintype "passive"))
    )
    (net (code "59") (name "Net-(T1A-B)") (class "Default")
      (node (ref "R11") (pin "2") (pinfunction "2_2") (pintype "passive"))
      (node (ref "T1") (pin "5") (pinfunction "B_5") (pintype "passive"))
    )
    (net (code "60") (name "Net-(T1B-B)") (class "Default")
      (node (ref "R12") (pin "2") (pinfunction "2_2") (pintype "passive"))
      (node (ref "T1") (pin "2") (pinfunction "B_2") (pintype "passive"))
    )
    (net (code "61") (name "Net-(U1-PROG)") (class "Default")
      (node (ref "R5") (pin "2") (pinfunction "2_2") (pintype "passive"))
      (node (ref "U1") (pin "5") (pinfunction "PROG_5") (pintype "bidirectional"))
    )
    (net (code "62") (name "Net-(U2-TMR)") (class "Default")
      (node (ref "C3") (pin "1") (pinfunction "1_1") (pintype "passive"))
      (node (ref "U2") (pin "3") (pinfunction "TMR_3") (pintype "bidirectional"))
    )
    (net (code "63") (name "Net-(U3-RXD)") (class "Default")
      (node (ref "JP2") (pin "P$1") (pinfunction "P$1_P$1") (pintype "bidirectional"))
      (node (ref "U3") (pin "25") (pinfunction "RXD_25") (pintype "bidirectional"))
    )
    (net (code "64") (name "Net-(U3-TXD)") (class "Default")
      (node (ref "JP1") (pin "P$1") (pinfunction "P$1_P$1") (pintype "bidirectional"))
      (node (ref "U3") (pin "26") (pinfunction "TXD_26") (pintype "bidirectional"))
    )
    (net (code "65") (name "Net-(U3-VDD)") (class "Default")
      (node (ref "C5") (pin "1") (pinfunction "1_1") (pintype "passive"))
      (node (ref "U3") (pin "6") (pinfunction "VDD_6") (pintype "bidirectional"))
    )
    (net (code "66") (name "Net-(U4-GPIO18)") (class "Default")
      (node (ref "TP6") (pin "TP") (pinfunction "TP_TP") (pintype "input"))
      (node (ref "U4") (pin "P$30") (pinfunction "GPIO18_P$30") (pintype "bidirectional"))
    )
    (net (code "67") (name "Net-(U4-GPIO19)") (class "Default")
      (node (ref "TP5") (pin "TP") (pinfunction "TP_TP") (pintype "input"))
      (node (ref "U4") (pin "P$31") (pinfunction "GPIO19_P$31") (pintype "bidirectional"))
    )
    (net (code "68") (name "Net-(U4-GPIO21)") (class "Default")
      (node (ref "TP3") (pin "TP") (pinfunction "TP_TP") (pintype "input"))
      (node (ref "U4") (pin "P$33") (pinfunction "GPIO21_P$33") (pintype "bidirectional"))
    )
    (net (code "69") (name "Net-(U4-NC)") (class "Default")
      (node (ref "TP4") (pin "TP") (pinfunction "TP_TP") (pintype "input"))
      (node (ref "U4") (pin "P$32") (pinfunction "NC_P$32") (pintype "bidirectional"))
    )
    (net (code "70") (name "Net-(U5-DS)") (class "Default")
      (node (ref "U5") (pin "14") (pinfunction "DS_14") (pintype "bidirectional"))
      (node (ref "U6") (pin "9") (pinfunction "Q7S_9") (pintype "bidirectional"))
    )
    (net (code "71") (name "unconnected-(LED5-GA-PadP$1)") (class "Default")
      (node (ref "LED5") (pin "P$1") (pinfunction "GA_P$1") (pintype "passive"))
    )
    (net (code "72") (name "unconnected-(LED5-GC-PadP$3)") (class "Default")
      (node (ref "LED5") (pin "P$3") (pinfunction "GC_P$3") (pintype "passive"))
    )
    (net (code "73") (name "unconnected-(LED5-RA-PadP$5)") (class "Default")
      (node (ref "LED5") (pin "P$5") (pinfunction "RA_P$5") (pintype "passive"))
    )
    (net (code "74") (name "unconnected-(LED5-RC-PadP$6)") (class "Default")
      (node (ref "LED5") (pin "P$6") (pinfunction "RC_P$6") (pintype "passive"))
    )
    (net (code "75") (name "unconnected-(P1-ID-Pad4)") (class "Default")
      (node (ref "P1") (pin "4") (pinfunction "ID_4") (pintype "bidirectional"))
    )
    (net (code "76") (name "unconnected-(U3-CTS-Pad23)") (class "Default")
      (node (ref "U3") (pin "23") (pinfunction "CTS_23") (pintype "bidirectional"))
    )
    (net (code "77") (name "unconnected-(U3-DCD-Pad1)") (class "Default")
      (node (ref "U3") (pin "1") (pinfunction "DCD_1") (pintype "bidirectional"))
    )
    (net (code "78") (name "unconnected-(U3-DSR-Pad27)") (class "Default")
      (node (ref "U3") (pin "27") (pinfunction "DSR_27") (pintype "bidirectional"))
    )
    (net (code "79") (name "unconnected-(U3-NC-Pad10)") (class "Default")
      (node (ref "U3") (pin "10") (pinfunction "NC_10") (pintype "bidirectional"))
    )
    (net (code "80") (name "unconnected-(U3-NC-Pad13)") (class "Default")
      (node (ref "U3") (pin "13") (pinfunction "NC_13") (pintype "bidirectional"))
    )
    (net (code "81") (name "unconnected-(U3-NC-Pad14)") (class "Default")
      (node (ref "U3") (pin "14") (pinfunction "NC_14") (pintype "bidirectional"))
    )
    (net (code "82") (name "unconnected-(U3-NC-Pad15)") (class "Default")
      (node (ref "U3") (pin "15") (pinfunction "NC_15") (pintype "bidirectional"))
    )
    (net (code "83") (name "unconnected-(U3-NC-Pad16)") (class "Default")
      (node (ref "U3") (pin "16") (pinfunction "NC_16") (pintype "bidirectional"))
    )
    (net (code "84") (name "unconnected-(U3-NC-Pad17)") (class "Default")
      (node (ref "U3") (pin "17") (pinfunction "NC_17") (pintype "bidirectional"))
    )
    (net (code "85") (name "unconnected-(U3-NC-Pad18)") (class "Default")
      (node (ref "U3") (pin "18") (pinfunction "NC_18") (pintype "bidirectional"))
    )
    (net (code "86") (name "unconnected-(U3-NC-Pad19)") (class "Default")
      (node (ref "U3") (pin "19") (pinfunction "NC_19") (pintype "bidirectional"))
    )
    (net (code "87") (name "unconnected-(U3-NC-Pad20)") (class "Default")
      (node (ref "U3") (pin "20") (pinfunction "NC_20") (pintype "bidirectional"))
    )
    (net (code "88") (name "unconnected-(U3-NC-Pad21)") (class "Default")
      (node (ref "U3") (pin "21") (pinfunction "NC_21") (pintype "bidirectional"))
    )
    (net (code "89") (name "unconnected-(U3-NC-Pad22)") (class "Default")
      (node (ref "U3") (pin "22") (pinfunction "NC_22") (pintype "bidirectional"))
    )
    (net (code "90") (name "unconnected-(U3-RI-Pad2)") (class "Default")
      (node (ref "U3") (pin "2") (pinfunction "RI_2") (pintype "bidirectional"))
    )
    (net (code "91") (name "unconnected-(U3-SUSPEND-Pad12)") (class "Default")
      (node (ref "U3") (pin "12") (pinfunction "SUSPEND_12") (pintype "bidirectional"))
    )
    (net (code "92") (name "unconnected-(U3-~{RST}-Pad9)") (class "Default")
      (node (ref "U3") (pin "9") (pinfunction "~{RST}_9") (pintype "bidirectional"))
    )
    (net (code "93") (name "unconnected-(U3-~{SUSPEND}-Pad11)") (class "Default")
      (node (ref "U3") (pin "11") (pinfunction "~{SUSPEND}_11") (pintype "bidirectional"))
    )
    (net (code "94") (name "unconnected-(U4-CLK-PadP$20)") (class "Default")
      (node (ref "U4") (pin "P$20") (pinfunction "CLK_P$20") (pintype "bidirectional"))
    )
    (net (code "95") (name "unconnected-(U4-GPIO2-PadP$24)") (class "Default")
      (node (ref "U4") (pin "P$24") (pinfunction "GPIO2_P$24") (pintype "bidirectional"))
    )
    (net (code "96") (name "unconnected-(U4-GPIO5-PadP$29)") (class "Default")
      (node (ref "U4") (pin "P$29") (pinfunction "GPIO5_P$29") (pintype "bidirectional"))
    )
    (net (code "97") (name "unconnected-(U4-GPIO12-PadP$14)") (class "Default")
      (node (ref "U4") (pin "P$14") (pinfunction "GPIO12_P$14") (pintype "bidirectional"))
    )
    (net (code "98") (name "unconnected-(U4-GPIO13-PadP$16)") (class "Default")
      (node (ref "U4") (pin "P$16") (pinfunction "GPIO13_P$16") (pintype "bidirectional"))
    )
    (net (code "99") (name "unconnected-(U4-GPIO15-PadP$23)") (class "Default")
      (node (ref "U4") (pin "P$23") (pinfunction "GPIO15_P$23") (pintype "bidirectional"))
    )
    (net (code "100") (name "unconnected-(U4-GPIO16-PadP$27)") (class "Default")
      (node (ref "U4") (pin "P$27") (pinfunction "GPIO16_P$27") (pintype "bidirectional"))
    )
    (net (code "101") (name "unconnected-(U4-GPIO17-PadP$28)") (class "Default")
      (node (ref "U4") (pin "P$28") (pinfunction "GPIO17_P$28") (pintype "bidirectional"))
    )
    (net (code "102") (name "unconnected-(U4-GPIO22-PadP$36)") (class "Default")
      (node (ref "U4") (pin "P$36") (pinfunction "GPIO22_P$36") (pintype "bidirectional"))
    )
    (net (code "103") (name "unconnected-(U4-GPIO23-PadP$37)") (class "Default")
      (node (ref "U4") (pin "P$37") (pinfunction "GPIO23_P$37") (pintype "bidirectional"))
    )
    (net (code "104") (name "unconnected-(U4-GPIO34-PadP$6)") (class "Default")
      (node (ref "U4") (pin "P$6") (pinfunction "GPIO34_P$6") (pintype "bidirectional"))
    )
    (net (code "105") (name "unconnected-(U5-Q6-Pad6)") (class "Default")
      (node (ref "U5") (pin "6") (pinfunction "Q6_6") (pintype "bidirectional"))
    )
    (net (code "106") (name "unconnected-(U5-Q7-Pad7)") (class "Default")
      (node (ref "U5") (pin "7") (pinfunction "Q7_7") (pintype "bidirectional"))
    )
    (net (code "107") (name "unconnected-(U5-Q7S-Pad9)") (class "Default")
      (node (ref "U5") (pin "9") (pinfunction "Q7S_9") (pintype "bidirectional"))
    )
    (net (code "108") (name "unconnected-(U6-Q6-Pad6)") (class "Default")
      (node (ref "U6") (pin "6") (pinfunction "Q6_6") (pintype "bidirectional"))
    )
    (net (code "109") (name "unconnected-(U6-Q7-Pad7)") (class "Default")
      (node (ref "U6") (pin "7") (pinfunction "Q7_7") (pintype "bidirectional"))
    )
  )
)
